# board.net
KiCad netlist of a schematic drawn in EAGLE
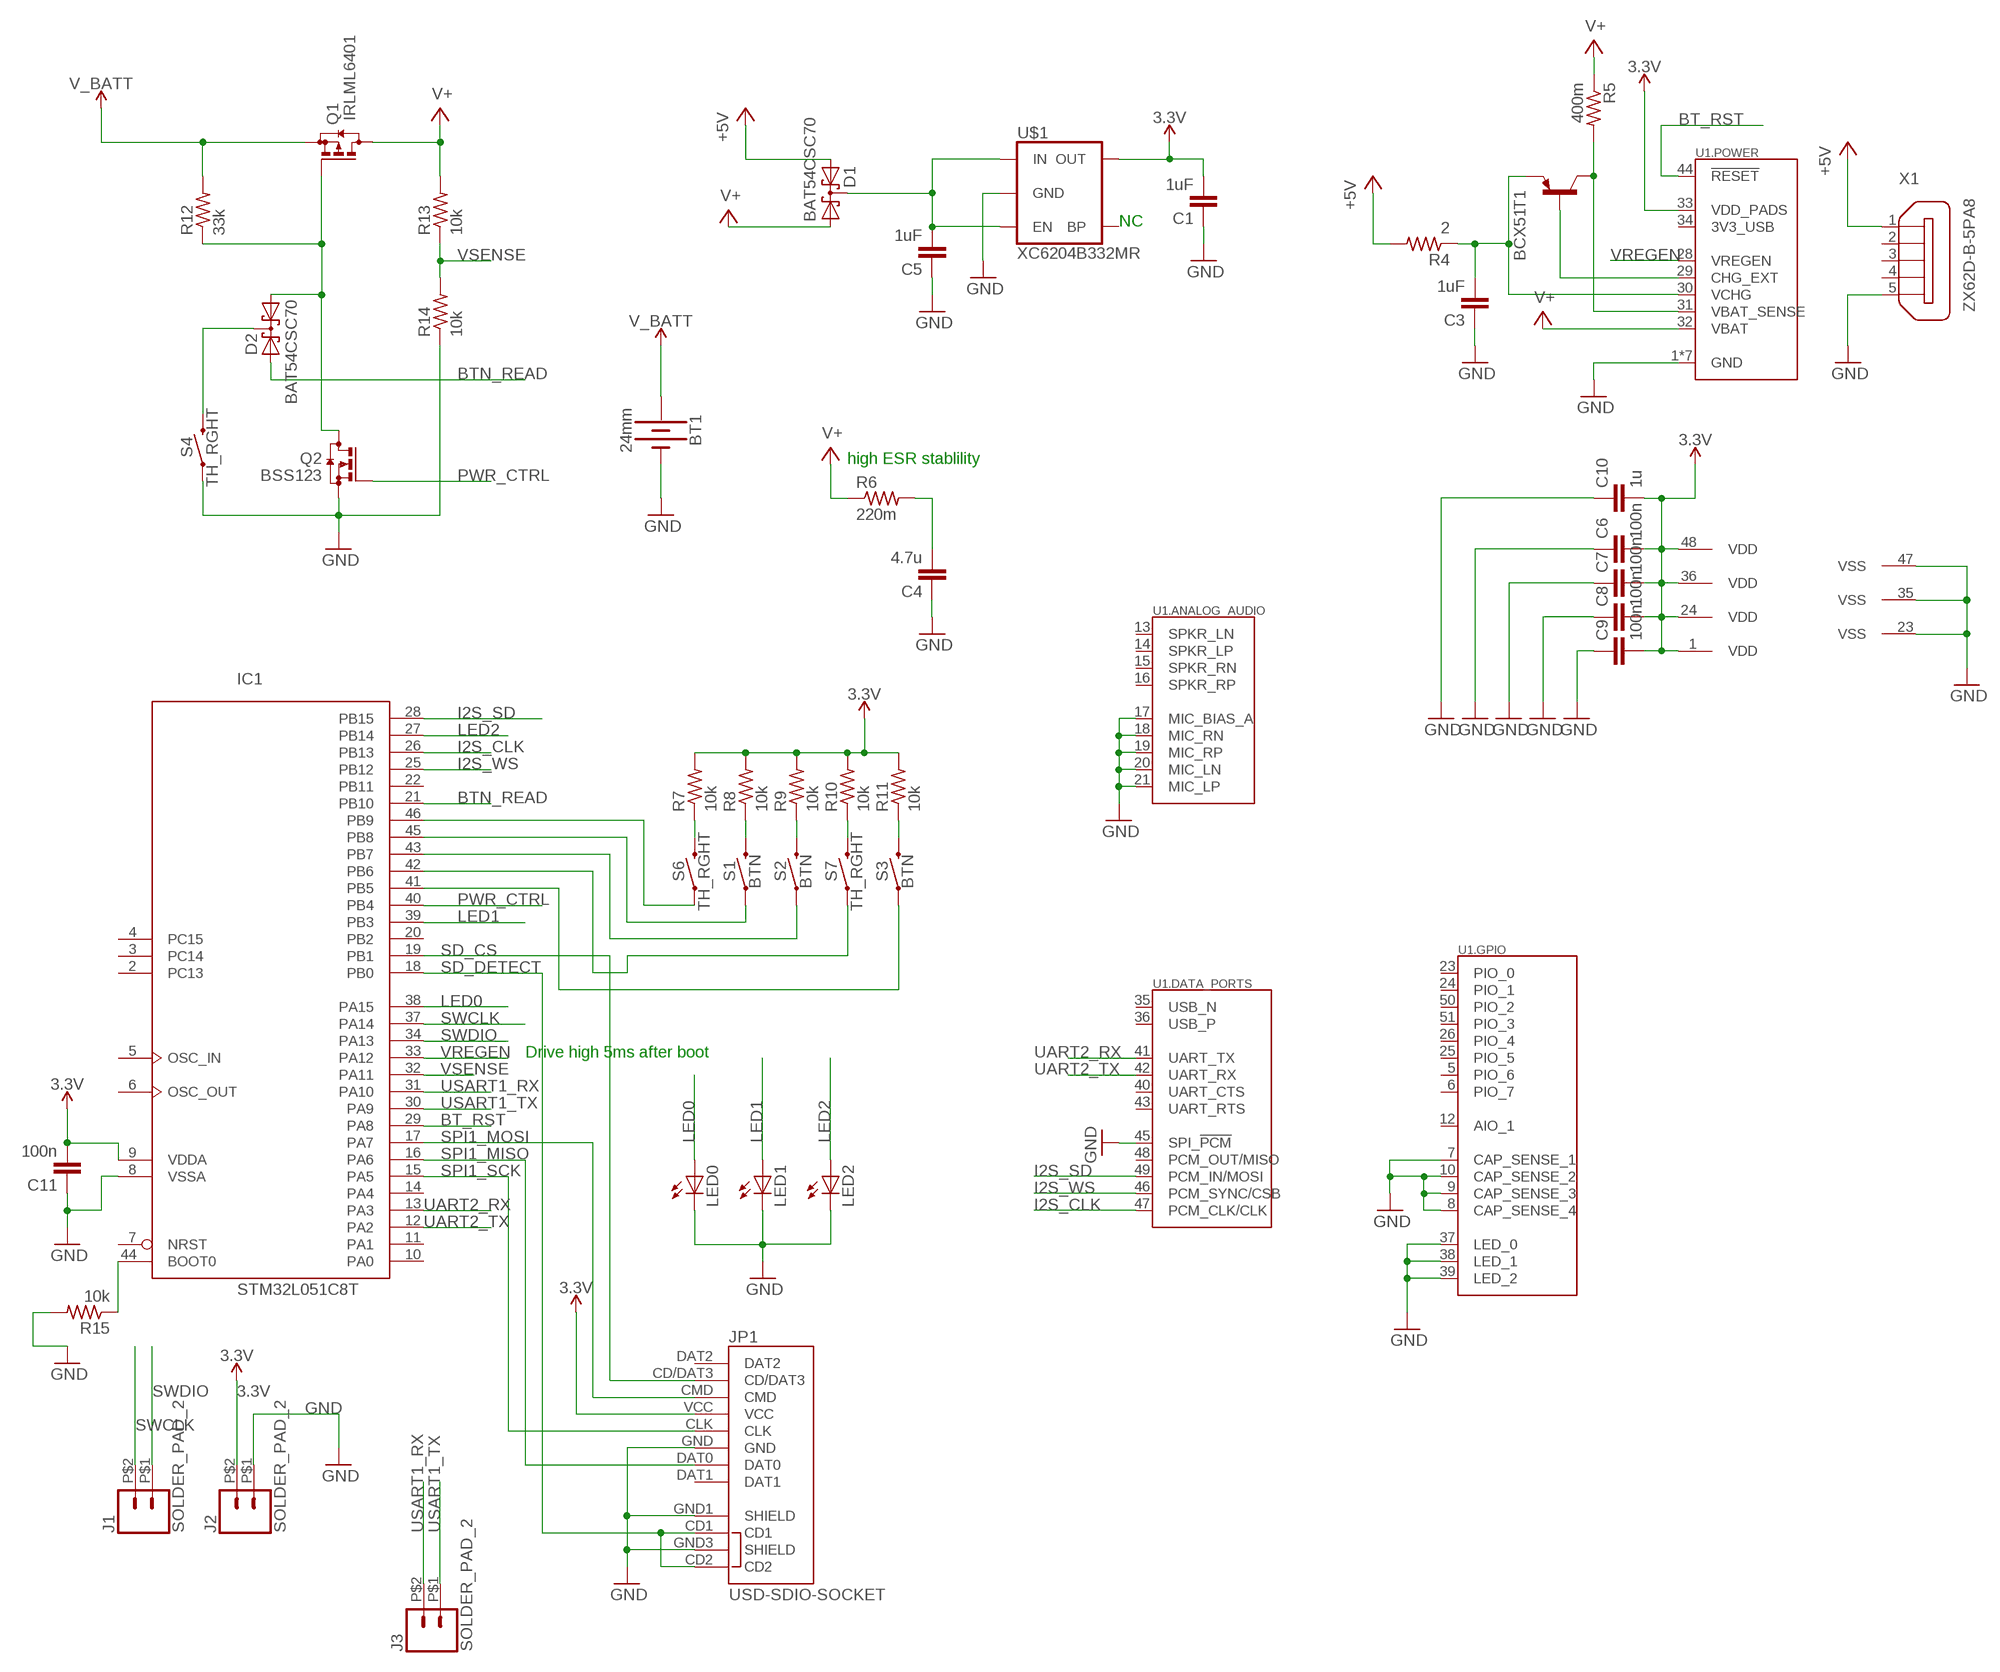
[diagram p0: schematic, sheet 1]

(export (version "E")
  (design (tool "Eeschema 10.0.6"))
  (components
    (comp (ref "BT1")
      (value "24mm")
      (footprint "eagle-import:BATTCON_24.5MM_PTH")
      (libsource (lib "eagle-import") (part "BATTERY-24.5MM_PTH"))
    )
    (comp (ref "C1")
      (value "1uF")
      (footprint "eagle-import:C1206")
      (libsource (lib "eagle-import") (part "C-EUC1206"))
    )
    (comp (ref "C3")
      (value "1uF")
      (footprint "eagle-import:C1206")
      (libsource (lib "eagle-import") (part "C-EUC1206"))
    )
    (comp (ref "C4")
      (value "4.7u")
      (footprint "eagle-import:C1206")
      (libsource (lib "eagle-import") (part "C-EUC1206"))
    )
    (comp (ref "C5")
      (value "1uF")
      (footprint "eagle-import:C1206")
      (libsource (lib "eagle-import") (part "C-EUC1206"))
    )
    (comp (ref "C6")
      (value "100n")
      (footprint "eagle-import:C0805")
      (libsource (lib "eagle-import") (part "C-EUC0805"))
    )
    (comp (ref "C7")
      (value "100n")
      (footprint "eagle-import:C0805")
      (libsource (lib "eagle-import") (part "C-EUC0805"))
    )
    (comp (ref "C8")
      (value "100n")
      (footprint "eagle-import:C0805")
      (libsource (lib "eagle-import") (part "C-EUC0805"))
    )
    (comp (ref "C9")
      (value "100n")
      (footprint "eagle-import:C0805")
      (libsource (lib "eagle-import") (part "C-EUC0805"))
    )
    (comp (ref "C10")
      (value "1u")
      (footprint "eagle-import:C0805")
      (libsource (lib "eagle-import") (part "C-EUC0805"))
    )
    (comp (ref "C11")
      (value "100n")
      (footprint "eagle-import:C0805")
      (libsource (lib "eagle-import") (part "C-EUC0805"))
    )
    (comp (ref "D1")
      (value "BAT54CSC70")
      (footprint "eagle-import:SOT323-R")
      (libsource (lib "eagle-import") (part "BAT54CSC70"))
    )
    (comp (ref "D2")
      (value "BAT54CSC70")
      (footprint "eagle-import:SOT323-R")
      (libsource (lib "eagle-import") (part "BAT54CSC70"))
    )
    (comp (ref "IC1")
      (value "STM32L051C8T")
      (footprint "eagle-import:LQFP48")
      (libsource (lib "eagle-import") (part "STM32L051CT8"))
    )
    (comp (ref "J1")
      (value "SOLDER_PAD_2")
      (footprint "eagle-import:SOLDER_PAD_2")
      (libsource (lib "eagle-import") (part "SOLDER_PAD_2"))
    )
    (comp (ref "J2")
      (value "SOLDER_PAD_2")
      (footprint "eagle-import:SOLDER_PAD_2")
      (libsource (lib "eagle-import") (part "SOLDER_PAD_2"))
    )
    (comp (ref "J3")
      (value "SOLDER_PAD_2")
      (footprint "eagle-import:SOLDER_PAD_2")
      (libsource (lib "eagle-import") (part "SOLDER_PAD_2"))
    )
    (comp (ref "JP1")
      (value "USD-SDIO-SOCKET")
      (footprint "eagle-import:MICRO-SD-SOCKET-SDIO")
      (libsource (lib "eagle-import") (part "USD-SDIO-SOCKET"))
    )
    (comp (ref "LED0")
      (value "LEDSML0805")
      (footprint "eagle-import:SML0805")
      (libsource (lib "eagle-import") (part "LEDSML0805"))
    )
    (comp (ref "LED1")
      (value "LEDSML0805")
      (footprint "eagle-import:SML0805")
      (libsource (lib "eagle-import") (part "LEDSML0805"))
    )
    (comp (ref "LED2")
      (value "LEDSML0805")
      (footprint "eagle-import:SML0805")
      (libsource (lib "eagle-import") (part "LEDSML0805"))
    )
    (comp (ref "Q1")
      (value "IRLML6401")
      (footprint "eagle-import:SOT23")
      (libsource (lib "eagle-import") (part "BSS84"))
    )
    (comp (ref "Q2")
      (value "BSS123")
      (footprint "eagle-import:SOT23")
      (libsource (lib "eagle-import") (part "BSS123"))
    )
    (comp (ref "R4")
      (value "2")
      (footprint "eagle-import:M1206")
      (libsource (lib "eagle-import") (part "R-US_M1206"))
    )
    (comp (ref "R5")
      (value "400m")
      (footprint "eagle-import:M1206")
      (libsource (lib "eagle-import") (part "R-US_M1206"))
    )
    (comp (ref "R6")
      (value "220m")
      (footprint "eagle-import:M1206")
      (libsource (lib "eagle-import") (part "R-US_M1206"))
    )
    (comp (ref "R7")
      (value "10k")
      (footprint "eagle-import:R0805")
      (libsource (lib "eagle-import") (part "resistor_R-US_R0805"))
    )
    (comp (ref "R8")
      (value "10k")
      (footprint "eagle-import:R0805")
      (libsource (lib "eagle-import") (part "resistor_R-US_R0805"))
    )
    (comp (ref "R9")
      (value "10k")
      (footprint "eagle-import:R0805")
      (libsource (lib "eagle-import") (part "resistor_R-US_R0805"))
    )
    (comp (ref "R10")
      (value "10k")
      (footprint "eagle-import:R0805")
      (libsource (lib "eagle-import") (part "resistor_R-US_R0805"))
    )
    (comp (ref "R11")
      (value "10k")
      (footprint "eagle-import:R0805")
      (libsource (lib "eagle-import") (part "resistor_R-US_R0805"))
    )
    (comp (ref "R12")
      (value "33k")
      (footprint "eagle-import:R0805")
      (libsource (lib "eagle-import") (part "resistor_R-US_R0805"))
    )
    (comp (ref "R13")
      (value "10k")
      (footprint "eagle-import:R0805")
      (libsource (lib "eagle-import") (part "resistor_R-US_R0805"))
    )
    (comp (ref "R14")
      (value "10k")
      (footprint "eagle-import:R0805")
      (libsource (lib "eagle-import") (part "resistor_R-US_R0805"))
    )
    (comp (ref "R15")
      (value "10k")
      (footprint "eagle-import:R0805")
      (libsource (lib "eagle-import") (part "resistor_R-US_R0805"))
    )
    (comp (ref "S1")
      (value "BTN")
      (footprint "eagle-import:TACTILE_SWITCH_SMD_6.2MM_TALL")
      (libsource (lib "eagle-import") (part "MOMENTARY-SWITCH-SPST-SMD-6.2MM-TALL"))
    )
    (comp (ref "S2")
      (value "BTN")
      (footprint "eagle-import:TACTILE_SWITCH_SMD_6.2MM_TALL")
      (libsource (lib "eagle-import") (part "MOMENTARY-SWITCH-SPST-SMD-6.2MM-TALL"))
    )
    (comp (ref "S3")
      (value "BTN")
      (footprint "eagle-import:TACTILE_SWITCH_SMD_6.2MM_TALL")
      (libsource (lib "eagle-import") (part "MOMENTARY-SWITCH-SPST-SMD-6.2MM-TALL"))
    )
    (comp (ref "S4")
      (value "TH_RGHT")
      (footprint "eagle-import:TACTILE_SWITCH_PTH_RIGHT_ANGLE")
      (libsource (lib "eagle-import") (part "MOMENTARY-SWITCH-SPST-PTH-RIGHT-ANGLE"))
    )
    (comp (ref "S6")
      (value "TH_RGHT")
      (footprint "eagle-import:TACTILE_SWITCH_PTH_RIGHT_ANGLE")
      (libsource (lib "eagle-import") (part "MOMENTARY-SWITCH-SPST-PTH-RIGHT-ANGLE"))
    )
    (comp (ref "S7")
      (value "TH_RGHT")
      (footprint "eagle-import:TACTILE_SWITCH_PTH_RIGHT_ANGLE")
      (libsource (lib "eagle-import") (part "MOMENTARY-SWITCH-SPST-PTH-RIGHT-ANGLE"))
    )
    (comp (ref "T1")
      (value "BCX51")
      (footprint "eagle-import:SOT89-ECB")
      (libsource (lib "eagle-import") (part "-PNP-SOT89-ECB"))
    )
    (comp (ref "U$1")
      (value "XC6204B332MR")
      (footprint "eagle-import:SOT23-5")
      (libsource (lib "eagle-import") (part "V_REG_SPX3819-SOT23-5"))
    )
    (comp (ref "U1")
      (value "BC127\"")
      (footprint "eagle-import:BC127")
      (libsource (lib "eagle-import") (part "BC127{dblquote}"))
    )
    (comp (ref "X1")
      (value "ZX62D-B-5PA8")
      (footprint "eagle-import:ZX62D-B-5PA8")
      (fields (field (name "MF") "Hirose"))
      (libsource (lib "eagle-import") (part "ZX62D-B-5PA8"))
    )
  )
  (nets
    (net (code "1") (name "+5V") (class "Default")
      (node (ref "D1") (pin "2") (pinfunction "A2_2") (pintype "passive"))
      (node (ref "R4") (pin "2") (pinfunction "2_2") (pintype "passive"))
      (node (ref "X1") (pin "1") (pinfunction "1_1") (pintype "passive"))
    )
    (net (code "2") (name "/BTN_READ") (class "Default")
      (node (ref "D2") (pin "2") (pinfunction "A2_2") (pintype "passive"))
      (node (ref "IC1") (pin "21") (pinfunction "PB10_21") (pintype "bidirectional"))
    )
    (net (code "3") (name "/BT_RST") (class "Default")
      (node (ref "IC1") (pin "29") (pinfunction "PA8_29") (pintype "bidirectional"))
      (node (ref "U1") (pin "44") (pinfunction "~{RESET}_44") (pintype "bidirectional"))
    )
    (net (code "4") (name "/I2S_CLK") (class "Default")
      (node (ref "IC1") (pin "26") (pinfunction "PB13_26") (pintype "bidirectional"))
      (node (ref "U1") (pin "47") (pinfunction "PCM_CLK/CLK_47") (pintype "bidirectional"))
    )
    (net (code "5") (name "/I2S_SD") (class "Default")
      (node (ref "IC1") (pin "28") (pinfunction "PB15_28") (pintype "bidirectional"))
      (node (ref "U1") (pin "49") (pinfunction "PCM_IN/MOSI_49") (pintype "bidirectional"))
    )
    (net (code "6") (name "/I2S_WS") (class "Default")
      (node (ref "IC1") (pin "25") (pinfunction "PB12_25") (pintype "bidirectional"))
      (node (ref "U1") (pin "46") (pinfunction "PCM_SYNC/CSB_46") (pintype "bidirectional"))
    )
    (net (code "7") (name "/LED0") (class "Default")
      (node (ref "IC1") (pin "38") (pinfunction "PA15_38") (pintype "bidirectional"))
      (node (ref "LED0") (pin "A") (pinfunction "A_A") (pintype "passive"))
    )
    (net (code "8") (name "/LED1") (class "Default")
      (node (ref "IC1") (pin "39") (pinfunction "PB3_39") (pintype "bidirectional"))
      (node (ref "LED1") (pin "A") (pinfunction "A_A") (pintype "passive"))
    )
    (net (code "9") (name "/LED2") (class "Default")
      (node (ref "IC1") (pin "27") (pinfunction "PB14_27") (pintype "bidirectional"))
      (node (ref "LED2") (pin "A") (pinfunction "A_A") (pintype "passive"))
    )
    (net (code "10") (name "/PWR_CTRL") (class "Default")
      (node (ref "IC1") (pin "40") (pinfunction "PB4_40") (pintype "bidirectional"))
      (node (ref "Q2") (pin "1") (pinfunction "G_1") (pintype "passive"))
    )
    (net (code "11") (name "/SD_CS") (class "Default")
      (node (ref "IC1") (pin "19") (pinfunction "PB1_19") (pintype "bidirectional"))
      (node (ref "JP1") (pin "CD/DAT3") (pinfunction "CD/DAT3_CD/DAT3") (pintype "bidirectional"))
    )
    (net (code "12") (name "/SD_DETECT") (class "Default")
      (node (ref "IC1") (pin "18") (pinfunction "PB0_18") (pintype "bidirectional"))
      (node (ref "JP1") (pin "CD1") (pinfunction "CD1_CD1") (pintype "bidirectional"))
      (node (ref "JP1") (pin "CD2") (pinfunction "CD2_CD2") (pintype "bidirectional"))
    )
    (net (code "13") (name "/SPI1_MISO") (class "Default")
      (node (ref "IC1") (pin "16") (pinfunction "PA6_16") (pintype "bidirectional"))
      (node (ref "JP1") (pin "DAT0") (pinfunction "DAT0_DAT0") (pintype "bidirectional"))
    )
    (net (code "14") (name "/SPI1_MOSI") (class "Default")
      (node (ref "IC1") (pin "17") (pinfunction "PA7_17") (pintype "bidirectional"))
      (node (ref "JP1") (pin "CMD") (pinfunction "CMD_CMD") (pintype "bidirectional"))
    )
    (net (code "15") (name "/SPI1_SCK") (class "Default")
      (node (ref "IC1") (pin "15") (pinfunction "PA5_15") (pintype "bidirectional"))
      (node (ref "JP1") (pin "CLK") (pinfunction "CLK_CLK") (pintype "bidirectional"))
    )
    (net (code "16") (name "/SWCLK") (class "Default")
      (node (ref "IC1") (pin "37") (pinfunction "PA14_37") (pintype "bidirectional"))
      (node (ref "J1") (pin "P$2") (pinfunction "2_P$2") (pintype "passive"))
    )
    (net (code "17") (name "/SWDIO") (class "Default")
      (node (ref "IC1") (pin "34") (pinfunction "PA13_34") (pintype "bidirectional"))
      (node (ref "J1") (pin "P$1") (pinfunction "1_P$1") (pintype "passive"))
    )
    (net (code "18") (name "/UART2_RX") (class "Default")
      (node (ref "IC1") (pin "13") (pinfunction "PA3_13") (pintype "bidirectional"))
      (node (ref "U1") (pin "41") (pinfunction "UART_TX_41") (pintype "bidirectional"))
    )
    (net (code "19") (name "/UART2_TX") (class "Default")
      (node (ref "IC1") (pin "12") (pinfunction "PA2_12") (pintype "bidirectional"))
      (node (ref "U1") (pin "42") (pinfunction "UART_RX_42") (pintype "bidirectional"))
    )
    (net (code "20") (name "/USART1_RX") (class "Default")
      (node (ref "IC1") (pin "31") (pinfunction "PA10_31") (pintype "bidirectional"))
      (node (ref "J3") (pin "P$2") (pinfunction "2_P$2") (pintype "passive"))
    )
    (net (code "21") (name "/USART1_TX") (class "Default")
      (node (ref "IC1") (pin "30") (pinfunction "PA9_30") (pintype "bidirectional"))
      (node (ref "J3") (pin "P$1") (pinfunction "1_P$1") (pintype "passive"))
    )
    (net (code "22") (name "/VREGEN") (class "Default")
      (node (ref "IC1") (pin "33") (pinfunction "PA12_33") (pintype "bidirectional"))
      (node (ref "U1") (pin "28") (pinfunction "VREGEN_28") (pintype "bidirectional"))
    )
    (net (code "23") (name "/VSENSE") (class "Default")
      (node (ref "IC1") (pin "32") (pinfunction "PA11_32") (pintype "bidirectional"))
      (node (ref "R13") (pin "1") (pinfunction "1_1") (pintype "passive"))
      (node (ref "R14") (pin "2") (pinfunction "2_2") (pintype "passive"))
    )
    (net (code "24") (name "3.3V") (class "Default")
      (node (ref "C1") (pin "2") (pinfunction "2_2") (pintype "passive"))
      (node (ref "C10") (pin "2") (pinfunction "2_2") (pintype "passive"))
      (node (ref "C11") (pin "2") (pinfunction "2_2") (pintype "passive"))
      (node (ref "C6") (pin "2") (pinfunction "2_2") (pintype "passive"))
      (node (ref "C7") (pin "2") (pinfunction "2_2") (pintype "passive"))
      (node (ref "C8") (pin "2") (pinfunction "2_2") (pintype "passive"))
      (node (ref "C9") (pin "2") (pinfunction "2_2") (pintype "passive"))
      (node (ref "IC1") (pin "1") (pinfunction "VDD_1") (pintype "power_in"))
      (node (ref "IC1") (pin "24") (pinfunction "VDD_24") (pintype "power_in"))
      (node (ref "IC1") (pin "36") (pinfunction "VDD_36") (pintype "power_in"))
      (node (ref "IC1") (pin "48") (pinfunction "VDD_48") (pintype "power_in"))
      (node (ref "IC1") (pin "9") (pinfunction "VDDA_9") (pintype "power_in"))
      (node (ref "J2") (pin "P$2") (pinfunction "2_P$2") (pintype "passive"))
      (node (ref "JP1") (pin "VCC") (pinfunction "VCC_VCC") (pintype "bidirectional"))
      (node (ref "R10") (pin "2") (pinfunction "2_2") (pintype "passive"))
      (node (ref "R11") (pin "2") (pinfunction "2_2") (pintype "passive"))
      (node (ref "R7") (pin "2") (pinfunction "2_2") (pintype "passive"))
      (node (ref "R8") (pin "2") (pinfunction "2_2") (pintype "passive"))
      (node (ref "R9") (pin "2") (pinfunction "2_2") (pintype "passive"))
      (node (ref "U$1") (pin "5") (pinfunction "OUT_5") (pintype "passive"))
      (node (ref "U1") (pin "33") (pinfunction "VDD_PADS_33") (pintype "bidirectional"))
    )
    (net (code "25") (name "GND") (class "Default")
      (node (ref "BT1") (pin "2") (pinfunction "-_2") (pintype "power_in"))
      (node (ref "C1") (pin "1") (pinfunction "1_1") (pintype "passive"))
      (node (ref "C10") (pin "1") (pinfunction "1_1") (pintype "passive"))
      (node (ref "C11") (pin "1") (pinfunction "1_1") (pintype "passive"))
      (node (ref "C3") (pin "1") (pinfunction "1_1") (pintype "passive"))
      (node (ref "C4") (pin "1") (pinfunction "1_1") (pintype "passive"))
      (node (ref "C5") (pin "1") (pinfunction "1_1") (pintype "passive"))
      (node (ref "C6") (pin "1") (pinfunction "1_1") (pintype "passive"))
      (node (ref "C7") (pin "1") (pinfunction "1_1") (pintype "passive"))
      (node (ref "C8") (pin "1") (pinfunction "1_1") (pintype "passive"))
      (node (ref "C9") (pin "1") (pinfunction "1_1") (pintype "passive"))
      (node (ref "IC1") (pin "23") (pinfunction "VSS_23") (pintype "power_in"))
      (node (ref "IC1") (pin "35") (pinfunction "VSS_35") (pintype "power_in"))
      (node (ref "IC1") (pin "47") (pinfunction "VSS_47") (pintype "power_in"))
      (node (ref "IC1") (pin "8") (pinfunction "VSSA_8") (pintype "power_in"))
      (node (ref "J2") (pin "P$1") (pinfunction "1_P$1") (pintype "passive"))
      (node (ref "JP1") (pin "GND") (pinfunction "GND_GND") (pintype "bidirectional"))
      (node (ref "JP1") (pin "GND1") (pinfunction "SHIELD_GND1") (pintype "bidirectional"))
      (node (ref "JP1") (pin "GND3") (pinfunction "SHIELD_GND3") (pintype "bidirectional"))
      (node (ref "LED0") (pin "C") (pinfunction "C_C") (pintype "passive"))
      (node (ref "LED1") (pin "C") (pinfunction "C_C") (pintype "passive"))
      (node (ref "LED2") (pin "C") (pinfunction "C_C") (pintype "passive"))
      (node (ref "Q2") (pin "2") (pinfunction "S_2") (pintype "passive"))
      (node (ref "R14") (pin "1") (pinfunction "1_1") (pintype "passive"))
      (node (ref "R15") (pin "2") (pinfunction "2_2") (pintype "passive"))
      (node (ref "S4") (pin "1") (pinfunction "1_1") (pintype "passive"))
      (node (ref "U$1") (pin "2") (pinfunction "GND_2") (pintype "input"))
      (node (ref "U1") (pin "1") (pinfunction "GND_1") (pintype "bidirectional"))
      (node (ref "U1") (pin "10") (pinfunction "CAP_SENSE_2_10") (pintype "bidirectional"))
      (node (ref "U1") (pin "11") (pinfunction "GND_11") (pintype "bidirectional"))
      (node (ref "U1") (pin "17") (pinfunction "MIC_BIAS_A_17") (pintype "bidirectional"))
      (node (ref "U1") (pin "18") (pinfunction "MIC_RN_18") (pintype "bidirectional"))
      (node (ref "U1") (pin "19") (pinfunction "MIC_RP_19") (pintype "bidirectional"))
      (node (ref "U1") (pin "2") (pinfunction "GND_2") (pintype "bidirectional"))
      (node (ref "U1") (pin "20") (pinfunction "MIC_LN_20") (pintype "bidirectional"))
      (node (ref "U1") (pin "21") (pinfunction "MIC_LP_21") (pintype "bidirectional"))
      (node (ref "U1") (pin "22") (pinfunction "GND_22") (pintype "bidirectional"))
      (node (ref "U1") (pin "27") (pinfunction "GND_27") (pintype "bidirectional"))
      (node (ref "U1") (pin "3") (pinfunction "GND_3") (pintype "bidirectional"))
      (node (ref "U1") (pin "37") (pinfunction "LED_0_37") (pintype "bidirectional"))
      (node (ref "U1") (pin "38") (pinfunction "LED_1_38") (pintype "bidirectional"))
      (node (ref "U1") (pin "39") (pinfunction "LED_2_39") (pintype "bidirectional"))
      (node (ref "U1") (pin "4") (pinfunction "GND_4") (pintype "bidirectional"))
      (node (ref "U1") (pin "45") (pinfunction "SPI_~{PCM}_45") (pintype "bidirectional"))
      (node (ref "U1") (pin "7") (pinfunction "CAP_SENSE_1_7") (pintype "bidirectional"))
      (node (ref "U1") (pin "8") (pinfunction "CAP_SENSE_4_8") (pintype "bidirectional"))
      (node (ref "U1") (pin "9") (pinfunction "CAP_SENSE_3_9") (pintype "bidirectional"))
      (node (ref "X1") (pin "5") (pinfunction "5_5") (pintype "passive"))
    )
    (net (code "26") (name "Net-(C4-Pad2)") (class "Default")
      (node (ref "C4") (pin "2") (pinfunction "2_2") (pintype "passive"))
      (node (ref "R6") (pin "2") (pinfunction "2_2") (pintype "passive"))
    )
    (net (code "27") (name "Net-(D1-CC)") (class "Default")
      (node (ref "C5") (pin "2") (pinfunction "2_2") (pintype "passive"))
      (node (ref "D1") (pin "3") (pinfunction "CC_3") (pintype "passive"))
      (node (ref "U$1") (pin "1") (pinfunction "IN_1") (pintype "input"))
      (node (ref "U$1") (pin "3") (pinfunction "EN_3") (pintype "input"))
    )
    (net (code "28") (name "Net-(D2-A1)") (class "Default")
      (node (ref "D2") (pin "1") (pinfunction "A1_1") (pintype "passive"))
      (node (ref "Q1") (pin "1") (pinfunction "G_1") (pintype "passive"))
      (node (ref "Q2") (pin "3") (pinfunction "D_3") (pintype "passive"))
      (node (ref "R12") (pin "1") (pinfunction "1_1") (pintype "passive"))
    )
    (net (code "29") (name "Net-(D2-CC)") (class "Default")
      (node (ref "D2") (pin "3") (pinfunction "CC_3") (pintype "passive"))
      (node (ref "S4") (pin "2") (pinfunction "2_2") (pintype "passive"))
    )
    (net (code "30") (name "Net-(IC1A-BOOT0)") (class "Default")
      (node (ref "IC1") (pin "44") (pinfunction "BOOT0_44") (pintype "input"))
      (node (ref "R15") (pin "1") (pinfunction "1_1") (pintype "passive"))
    )
    (net (code "31") (name "Net-(IC1A-PB5)") (class "Default")
      (node (ref "IC1") (pin "41") (pinfunction "PB5_41") (pintype "bidirectional"))
      (node (ref "S3") (pin "A2") (pinfunction "1_A2") (pintype "passive"))
    )
    (net (code "32") (name "Net-(IC1A-PB6)") (class "Default")
      (node (ref "IC1") (pin "42") (pinfunction "PB6_42") (pintype "bidirectional"))
      (node (ref "S7") (pin "1") (pinfunction "1_1") (pintype "passive"))
    )
    (net (code "33") (name "Net-(IC1A-PB7)") (class "Default")
      (node (ref "IC1") (pin "43") (pinfunction "PB7_43") (pintype "bidirectional"))
      (node (ref "S2") (pin "A2") (pinfunction "1_A2") (pintype "passive"))
    )
    (net (code "34") (name "Net-(IC1A-PB8)") (class "Default")
      (node (ref "IC1") (pin "45") (pinfunction "PB8_45") (pintype "bidirectional"))
      (node (ref "S1") (pin "A2") (pinfunction "1_A2") (pintype "passive"))
    )
    (net (code "35") (name "Net-(IC1A-PB9)") (class "Default")
      (node (ref "IC1") (pin "46") (pinfunction "PB9_46") (pintype "bidirectional"))
      (node (ref "S6") (pin "1") (pinfunction "1_1") (pintype "passive"))
    )
    (net (code "36") (name "Net-(R7-Pad1)") (class "Default")
      (node (ref "R7") (pin "1") (pinfunction "1_1") (pintype "passive"))
      (node (ref "S6") (pin "2") (pinfunction "2_2") (pintype "passive"))
    )
    (net (code "37") (name "Net-(R10-Pad1)") (class "Default")
      (node (ref "R10") (pin "1") (pinfunction "1_1") (pintype "passive"))
      (node (ref "S7") (pin "2") (pinfunction "2_2") (pintype "passive"))
    )
    (net (code "38") (name "Net-(S1-2)") (class "Default")
      (node (ref "R8") (pin "1") (pinfunction "1_1") (pintype "passive"))
      (node (ref "S1") (pin "B2") (pinfunction "2_B2") (pintype "passive"))
    )
    (net (code "39") (name "Net-(S2-2)") (class "Default")
      (node (ref "R9") (pin "1") (pinfunction "1_1") (pintype "passive"))
      (node (ref "S2") (pin "B2") (pinfunction "2_B2") (pintype "passive"))
    )
    (net (code "40") (name "Net-(S3-2)") (class "Default")
      (node (ref "R11") (pin "1") (pinfunction "1_1") (pintype "passive"))
      (node (ref "S3") (pin "B2") (pinfunction "2_B2") (pintype "passive"))
    )
    (net (code "41") (name "Net-(U1D-CHG_EXT)") (class "Default")
      (node (ref "T1") (pin "B") (pinfunction "B_B") (pintype "passive"))
      (node (ref "U1") (pin "29") (pinfunction "CHG_EXT_29") (pintype "bidirectional"))
    )
    (net (code "42") (name "Net-(U1D-VBAT_SENSE)") (class "Default")
      (node (ref "R5") (pin "2") (pinfunction "2_2") (pintype "passive"))
      (node (ref "T1") (pin "C") (pinfunction "C_C") (pintype "passive"))
      (node (ref "U1") (pin "31") (pinfunction "VBAT_SENSE_31") (pintype "bidirectional"))
    )
    (net (code "43") (name "Net-(U1D-VCHG)") (class "Default")
      (node (ref "C3") (pin "2") (pinfunction "2_2") (pintype "passive"))
      (node (ref "R4") (pin "1") (pinfunction "1_1") (pintype "passive"))
      (node (ref "T1") (pin "E") (pinfunction "E_E") (pintype "passive"))
      (node (ref "U1") (pin "30") (pinfunction "VCHG_30") (pintype "bidirectional"))
    )
    (net (code "44") (name "V+") (class "Default")
      (node (ref "D1") (pin "1") (pinfunction "A1_1") (pintype "passive"))
      (node (ref "Q1") (pin "3") (pinfunction "D_3") (pintype "passive"))
      (node (ref "R13") (pin "2") (pinfunction "2_2") (pintype "passive"))
      (node (ref "R5") (pin "1") (pinfunction "1_1") (pintype "passive"))
      (node (ref "R6") (pin "1") (pinfunction "1_1") (pintype "passive"))
      (node (ref "U1") (pin "32") (pinfunction "VBAT_32") (pintype "bidirectional"))
    )
    (net (code "45") (name "V_BATT") (class "Default")
      (node (ref "BT1") (pin "3") (pinfunction "+_3") (pintype "power_in"))
      (node (ref "Q1") (pin "2") (pinfunction "S_2") (pintype "passive"))
      (node (ref "R12") (pin "2") (pinfunction "2_2") (pintype "passive"))
    )
    (net (code "46") (name "unconnected-(IC1A-NRST-Pad7)") (class "Default")
      (node (ref "IC1") (pin "7") (pinfunction "NRST_7") (pintype "bidirectional"))
    )
    (net (code "47") (name "unconnected-(IC1A-OSC_IN-Pad5)") (class "Default")
      (node (ref "IC1") (pin "5") (pinfunction "OSC_IN_5") (pintype "bidirectional"))
    )
    (net (code "48") (name "unconnected-(IC1A-OSC_OUT-Pad6)") (class "Default")
      (node (ref "IC1") (pin "6") (pinfunction "OSC_OUT_6") (pintype "bidirectional"))
    )
    (net (code "49") (name "unconnected-(IC1A-PA0-Pad10)") (class "Default")
      (node (ref "IC1") (pin "10") (pinfunction "PA0_10") (pintype "bidirectional"))
    )
    (net (code "50") (name "unconnected-(IC1A-PA1-Pad11)") (class "Default")
      (node (ref "IC1") (pin "11") (pinfunction "PA1_11") (pintype "bidirectional"))
    )
    (net (code "51") (name "unconnected-(IC1A-PA4-Pad14)") (class "Default")
      (node (ref "IC1") (pin "14") (pinfunction "PA4_14") (pintype "bidirectional"))
    )
    (net (code "52") (name "unconnected-(IC1A-PB2-Pad20)") (class "Default")
      (node (ref "IC1") (pin "20") (pinfunction "PB2_20") (pintype "bidirectional"))
    )
    (net (code "53") (name "unconnected-(IC1A-PB11-Pad22)") (class "Default")
      (node (ref "IC1") (pin "22") (pinfunction "PB11_22") (pintype "bidirectional"))
    )
    (net (code "54") (name "unconnected-(IC1A-PC13-Pad2)") (class "Default")
      (node (ref "IC1") (pin "2") (pinfunction "PC13_2") (pintype "bidirectional"))
    )
    (net (code "55") (name "unconnected-(IC1A-PC14-Pad3)") (class "Default")
      (node (ref "IC1") (pin "3") (pinfunction "PC14_3") (pintype "bidirectional"))
    )
    (net (code "56") (name "unconnected-(IC1A-PC15-Pad4)") (class "Default")
      (node (ref "IC1") (pin "4") (pinfunction "PC15_4") (pintype "bidirectional"))
    )
    (net (code "57") (name "unconnected-(JP1-PadDAT1)") (class "Default")
      (node (ref "JP1") (pin "DAT1") (pinfunction "DAT1_DAT1") (pintype "bidirectional"))
    )
    (net (code "58") (name "unconnected-(JP1-PadDAT2)") (class "Default")
      (node (ref "JP1") (pin "DAT2") (pinfunction "DAT2_DAT2") (pintype "bidirectional"))
    )
    (net (code "59") (name "unconnected-(U$1-BP-Pad4)") (class "Default")
      (node (ref "U$1") (pin "4") (pinfunction "BP_4") (pintype "input"))
    )
    (net (code "60") (name "unconnected-(U1A-SPKR_LN-Pad13)") (class "Default")
      (node (ref "U1") (pin "13") (pinfunction "SPKR_LN_13") (pintype "bidirectional"))
    )
    (net (code "61") (name "unconnected-(U1A-SPKR_LP-Pad14)") (class "Default")
      (node (ref "U1") (pin "14") (pinfunction "SPKR_LP_14") (pintype "bidirectional"))
    )
    (net (code "62") (name "unconnected-(U1A-SPKR_RN-Pad15)") (class "Default")
      (node (ref "U1") (pin "15") (pinfunction "SPKR_RN_15") (pintype "bidirectional"))
    )
    (net (code "63") (name "unconnected-(U1A-SPKR_RP-Pad16)") (class "Default")
      (node (ref "U1") (pin "16") (pinfunction "SPKR_RP_16") (pintype "bidirectional"))
    )
    (net (code "64") (name "unconnected-(U1B-PCM_OUT{slash}MISO-Pad48)") (class "Default")
      (node (ref "U1") (pin "48") (pinfunction "PCM_OUT/MISO_48") (pintype "bidirectional"))
    )
    (net (code "65") (name "unconnected-(U1B-UART_CTS-Pad40)") (class "Default")
      (node (ref "U1") (pin "40") (pinfunction "UART_CTS_40") (pintype "bidirectional"))
    )
    (net (code "66") (name "unconnected-(U1B-UART_RTS-Pad43)") (class "Default")
      (node (ref "U1") (pin "43") (pinfunction "UART_RTS_43") (pintype "bidirectional"))
    )
    (net (code "67") (name "unconnected-(U1B-USB_N-Pad35)") (class "Default")
      (node (ref "U1") (pin "35") (pinfunction "USB_N_35") (pintype "bidirectional"))
    )
    (net (code "68") (name "unconnected-(U1B-USB_P-Pad36)") (class "Default")
      (node (ref "U1") (pin "36") (pinfunction "USB_P_36") (pintype "bidirectional"))
    )
    (net (code "69") (name "unconnected-(U1C-AIO_1-Pad12)") (class "Default")
      (node (ref "U1") (pin "12") (pinfunction "AIO_1_12") (pintype "bidirectional"))
    )
    (net (code "70") (name "unconnected-(U1C-PIO_0-Pad23)") (class "Default")
      (node (ref "U1") (pin "23") (pinfunction "PIO_0_23") (pintype "bidirectional"))
    )
    (net (code "71") (name "unconnected-(U1C-PIO_1-Pad24)") (class "Default")
      (node (ref "U1") (pin "24") (pinfunction "PIO_1_24") (pintype "bidirectional"))
    )
    (net (code "72") (name "unconnected-(U1C-PIO_2-Pad50)") (class "Default")
      (node (ref "U1") (pin "50") (pinfunction "PIO_2_50") (pintype "bidirectional"))
    )
    (net (code "73") (name "unconnected-(U1C-PIO_3-Pad51)") (class "Default")
      (node (ref "U1") (pin "51") (pinfunction "PIO_3_51") (pintype "bidirectional"))
    )
    (net (code "74") (name "unconnected-(U1C-PIO_4-Pad26)") (class "Default")
      (node (ref "U1") (pin "26") (pinfunction "PIO_4_26") (pintype "bidirectional"))
    )
    (net (code "75") (name "unconnected-(U1C-PIO_5-Pad25)") (class "Default")
      (node (ref "U1") (pin "25") (pinfunction "PIO_5_25") (pintype "bidirectional"))
    )
    (net (code "76") (name "unconnected-(U1C-PIO_6-Pad5)") (class "Default")
      (node (ref "U1") (pin "5") (pinfunction "PIO_6_5") (pintype "bidirectional"))
    )
    (net (code "77") (name "unconnected-(U1C-PIO_7-Pad6)") (class "Default")
      (node (ref "U1") (pin "6") (pinfunction "PIO_7_6") (pintype "bidirectional"))
    )
    (net (code "78") (name "unconnected-(U1D-3V3_USB-Pad34)") (class "Default")
      (node (ref "U1") (pin "34") (pinfunction "3V3_USB_34") (pintype "bidirectional"))
    )
    (net (code "79") (name "unconnected-(X1-Pad2)") (class "Default")
      (node (ref "X1") (pin "2") (pinfunction "2_2") (pintype "passive"))
    )
    (net (code "80") (name "unconnected-(X1-Pad3)") (class "Default")
      (node (ref "X1") (pin "3") (pinfunction "3_3") (pintype "passive"))
    )
    (net (code "81") (name "unconnected-(X1-Pad4)") (class "Default")
      (node (ref "X1") (pin "4") (pinfunction "4_4") (pintype "passive"))
    )
  )
)
